# untitled.net
KiCad netlist of a schematic drawn in EAGLE
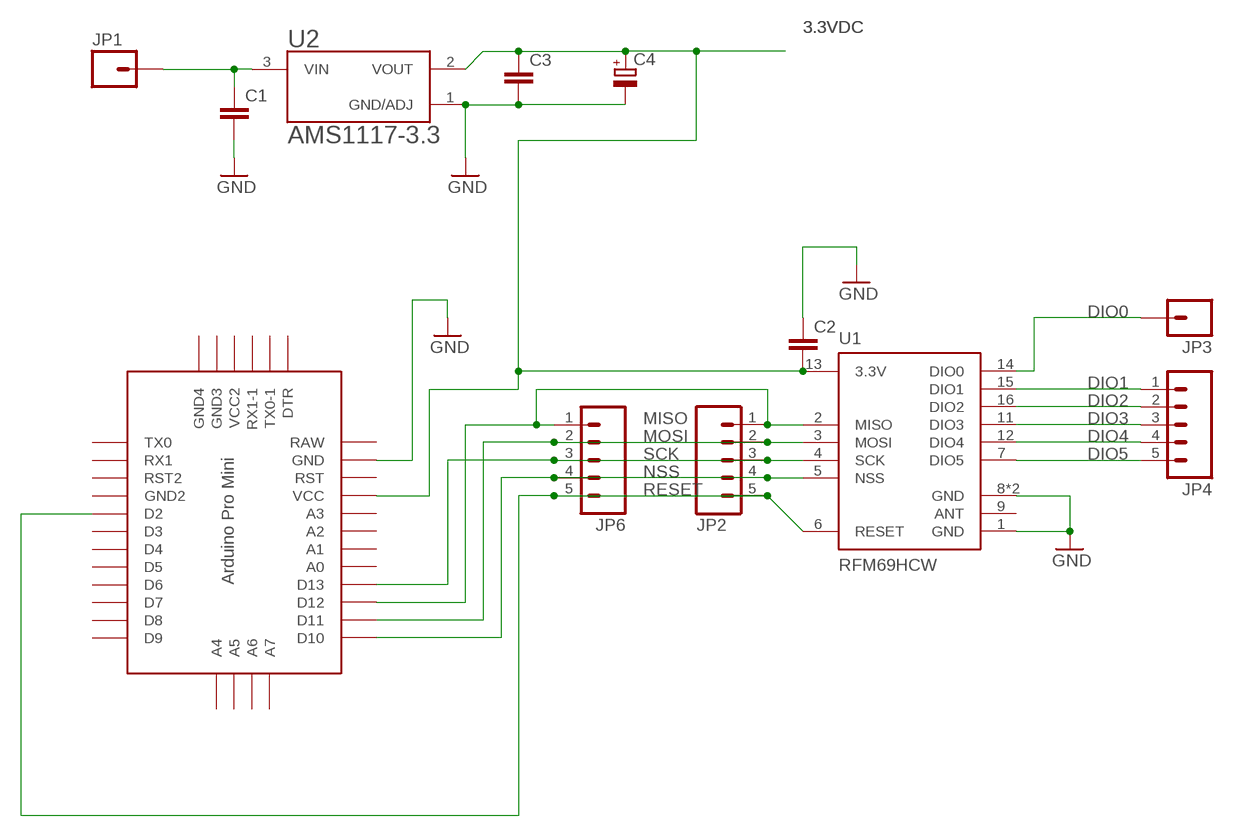
[diagram p0: schematic, sheet 1]

(export (version "E")
  (design (tool "Eeschema 10.0.6"))
  (components
    (comp (ref "C1")
      (value "C-EU025-030X050")
      (footprint "eagle-import:C025-030X050")
      (libsource (lib "eagle-import") (part "C-EU025-030X050"))
    )
    (comp (ref "C2")
      (value "C-EU025-030X050")
      (footprint "eagle-import:C025-030X050")
      (libsource (lib "eagle-import") (part "C-EU025-030X050"))
    )
    (comp (ref "C3")
      (value "C-EU025-030X050")
      (footprint "eagle-import:C025-030X050")
      (libsource (lib "eagle-import") (part "C-EU025-030X050"))
    )
    (comp (ref "C4")
      (value "CPOL-EUE5-8.5")
      (footprint "eagle-import:E5-8,5")
      (libsource (lib "eagle-import") (part "CPOL-EUE5-8.5"))
    )
    (comp (ref "JP1")
      (value "M01SMDNS")
      (footprint "eagle-import:1X01NS")
      (libsource (lib "eagle-import") (part "M01SMDNS"))
    )
    (comp (ref "JP2")
      (value "M05_ROUNDONLY_NOSILK")
      (footprint "eagle-import:1X05_ROUNDONLY_NOSILK")
      (libsource (lib "eagle-import") (part "M05_ROUNDONLY_NOSILK"))
    )
    (comp (ref "JP3")
      (value "M01SMDNS")
      (footprint "eagle-import:1X01NS")
      (libsource (lib "eagle-import") (part "M01SMDNS"))
    )
    (comp (ref "JP4")
      (value "M05_ROUNDONLY_NOSILK")
      (footprint "eagle-import:1X05_ROUNDONLY_NOSILK")
      (libsource (lib "eagle-import") (part "M05_ROUNDONLY_NOSILK"))
    )
    (comp (ref "JP6")
      (value "M05_ROUNDONLY_NOSILK")
      (footprint "eagle-import:1X05_ROUNDONLY_NOSILK")
      (libsource (lib "eagle-import") (part "M05_ROUNDONLY_NOSILK"))
    )
    (comp (ref "U$1")
      (value "PRO-MINI")
      (footprint "eagle-import:PRO-MINI")
      (libsource (lib "eagle-import") (part "PRO-MINI"))
    )
    (comp (ref "U1")
      (value "RFM69HCW")
      (footprint "eagle-import:RFM69HCW-XXXS2")
      (libsource (lib "eagle-import") (part "RFM69HCW"))
    )
    (comp (ref "U2")
      (value "AMS1117-3.3")
      (footprint "eagle-import:SOT229P700X180-4N")
      (fields (field (name "MF") "Advanced Monolithic Systems"))
      (libsource (lib "eagle-import") (part "AMS1117-3.3"))
    )
  )
  (nets
    (net (code "1") (name "/3.3VDC") (class "Default")
      (node (ref "C2") (pin "2") (pinfunction "2_2") (pintype "passive"))
      (node (ref "C3") (pin "1") (pinfunction "1_1") (pintype "passive"))
      (node (ref "C4") (pin "+") (pinfunction "+_+") (pintype "passive"))
      (node (ref "U$1") (pin "VCC") (pinfunction "VCC_VCC") (pintype "bidirectional"))
      (node (ref "U1") (pin "13") (pinfunction "3.3V_13") (pintype "power_in"))
      (node (ref "U2") (pin "2") (pinfunction "VOUT_2") (pintype "output"))
    )
    (net (code "2") (name "/DIO0") (class "Default")
      (node (ref "JP3") (pin "1") (pinfunction "1_1") (pintype "passive"))
      (node (ref "U1") (pin "14") (pinfunction "DIO0_14") (pintype "bidirectional"))
    )
    (net (code "3") (name "/DIO1") (class "Default")
      (node (ref "JP4") (pin "1") (pinfunction "1_1") (pintype "passive"))
      (node (ref "U1") (pin "15") (pinfunction "DIO1_15") (pintype "bidirectional"))
    )
    (net (code "4") (name "/DIO2") (class "Default")
      (node (ref "JP4") (pin "2") (pinfunction "2_2") (pintype "passive"))
      (node (ref "U1") (pin "16") (pinfunction "DIO2_16") (pintype "bidirectional"))
    )
    (net (code "5") (name "/DIO3") (class "Default")
      (node (ref "JP4") (pin "3") (pinfunction "3_3") (pintype "passive"))
      (node (ref "U1") (pin "11") (pinfunction "DIO3_11") (pintype "bidirectional"))
    )
    (net (code "6") (name "/DIO4") (class "Default")
      (node (ref "JP4") (pin "4") (pinfunction "4_4") (pintype "passive"))
      (node (ref "U1") (pin "12") (pinfunction "DIO4_12") (pintype "bidirectional"))
    )
    (net (code "7") (name "/DIO5") (class "Default")
      (node (ref "JP4") (pin "5") (pinfunction "5_5") (pintype "passive"))
      (node (ref "U1") (pin "7") (pinfunction "DIO5_7") (pintype "bidirectional"))
    )
    (net (code "8") (name "/MISO") (class "Default")
      (node (ref "JP2") (pin "1") (pinfunction "1_1") (pintype "passive"))
      (node (ref "JP6") (pin "1") (pinfunction "1_1") (pintype "passive"))
      (node (ref "U$1") (pin "D12") (pinfunction "D12_D12") (pintype "bidirectional"))
      (node (ref "U1") (pin "2") (pinfunction "MISO_2") (pintype "bidirectional"))
    )
    (net (code "9") (name "/MOSI") (class "Default")
      (node (ref "JP2") (pin "2") (pinfunction "2_2") (pintype "passive"))
      (node (ref "JP6") (pin "2") (pinfunction "2_2") (pintype "passive"))
      (node (ref "U$1") (pin "D11") (pinfunction "D11_D11") (pintype "bidirectional"))
      (node (ref "U1") (pin "3") (pinfunction "MOSI_3") (pintype "input"))
    )
    (net (code "10") (name "/NSS") (class "Default")
      (node (ref "JP2") (pin "4") (pinfunction "4_4") (pintype "passive"))
      (node (ref "JP6") (pin "4") (pinfunction "4_4") (pintype "passive"))
      (node (ref "U$1") (pin "D10") (pinfunction "D10_D10") (pintype "bidirectional"))
      (node (ref "U1") (pin "5") (pinfunction "NSS_5") (pintype "input"))
    )
    (net (code "11") (name "/RAW") (class "Default")
      (node (ref "U$1") (pin "RAW") (pinfunction "RAW_RAW") (pintype "power_in"))
    )
    (net (code "12") (name "/RESET") (class "Default")
      (node (ref "JP2") (pin "5") (pinfunction "5_5") (pintype "passive"))
      (node (ref "JP6") (pin "5") (pinfunction "5_5") (pintype "passive"))
      (node (ref "U$1") (pin "D2") (pinfunction "D2_D2") (pintype "bidirectional"))
      (node (ref "U1") (pin "6") (pinfunction "RESET_6") (pintype "input"))
    )
    (net (code "13") (name "/SCK") (class "Default")
      (node (ref "JP2") (pin "3") (pinfunction "3_3") (pintype "passive"))
      (node (ref "JP6") (pin "3") (pinfunction "3_3") (pintype "passive"))
      (node (ref "U$1") (pin "D13") (pinfunction "D13_D13") (pintype "bidirectional"))
      (node (ref "U1") (pin "4") (pinfunction "SCK_4") (pintype "input"))
    )
    (net (code "14") (name "GND") (class "Default")
      (node (ref "C1") (pin "2") (pinfunction "2_2") (pintype "passive"))
      (node (ref "C2") (pin "1") (pinfunction "1_1") (pintype "passive"))
      (node (ref "C3") (pin "2") (pinfunction "2_2") (pintype "passive"))
      (node (ref "C4") (pin "-") (pinfunction "-_-") (pintype "passive"))
      (node (ref "U$1") (pin "GND") (pinfunction "GND_GND") (pintype "input"))
      (node (ref "U1") (pin "1") (pinfunction "GND_1") (pintype "power_in"))
      (node (ref "U1") (pin "10") (pinfunction "GND_10") (pintype "power_in"))
      (node (ref "U1") (pin "8") (pinfunction "GND_8") (pintype "power_in"))
      (node (ref "U2") (pin "1") (pinfunction "GND/ADJ_1") (pintype "power_in"))
    )
    (net (code "15") (name "Net-(U2-VIN)") (class "Default")
      (node (ref "C1") (pin "1") (pinfunction "1_1") (pintype "passive"))
      (node (ref "JP1") (pin "1") (pinfunction "1_1") (pintype "passive"))
      (node (ref "U2") (pin "3") (pinfunction "VIN_3") (pintype "input"))
    )
    (net (code "16") (name "unconnected-(U$1-GND2-PadGND1)") (class "Default")
      (node (ref "U$1") (pin "GND1") (pinfunction "GND2_GND1") (pintype "bidirectional"))
    )
    (net (code "17") (name "unconnected-(U$1-GND4-PadGND2)") (class "Default")
      (node (ref "U$1") (pin "GND2") (pinfunction "GND4_GND2") (pintype "bidirectional"))
    )
    (net (code "18") (name "unconnected-(U$1-PadA0)") (class "Default")
      (node (ref "U$1") (pin "A0") (pinfunction "A0_A0") (pintype "bidirectional"))
    )
    (net (code "19") (name "unconnected-(U$1-PadA1)") (class "Default")
      (node (ref "U$1") (pin "A1") (pinfunction "A1_A1") (pintype "bidirectional"))
    )
    (net (code "20") (name "unconnected-(U$1-PadA2)") (class "Default")
      (node (ref "U$1") (pin "A2") (pinfunction "A2_A2") (pintype "bidirectional"))
    )
    (net (code "21") (name "unconnected-(U$1-PadA3)") (class "Default")
      (node (ref "U$1") (pin "A3") (pinfunction "A3_A3") (pintype "bidirectional"))
    )
    (net (code "22") (name "unconnected-(U$1-PadA4)") (class "Default")
      (node (ref "U$1") (pin "A4") (pinfunction "A4_A4") (pintype "bidirectional"))
    )
    (net (code "23") (name "unconnected-(U$1-PadA5)") (class "Default")
      (node (ref "U$1") (pin "A5") (pinfunction "A5_A5") (pintype "bidirectional"))
    )
    (net (code "24") (name "unconnected-(U$1-PadA6)") (class "Default")
      (node (ref "U$1") (pin "A6") (pinfunction "A6_A6") (pintype "bidirectional"))
    )
    (net (code "25") (name "unconnected-(U$1-PadA7)") (class "Default")
      (node (ref "U$1") (pin "A7") (pinfunction "A7_A7") (pintype "bidirectional"))
    )
    (net (code "26") (name "unconnected-(U$1-PadD3)") (class "Default")
      (node (ref "U$1") (pin "D3") (pinfunction "D3_D3") (pintype "bidirectional"))
    )
    (net (code "27") (name "unconnected-(U$1-PadD4)") (class "Default")
      (node (ref "U$1") (pin "D4") (pinfunction "D4_D4") (pintype "bidirectional"))
    )
    (net (code "28") (name "unconnected-(U$1-PadD5)") (class "Default")
      (node (ref "U$1") (pin "D5") (pinfunction "D5_D5") (pintype "bidirectional"))
    )
    (net (code "29") (name "unconnected-(U$1-PadD6)") (class "Default")
      (node (ref "U$1") (pin "D6") (pinfunction "D6_D6") (pintype "bidirectional"))
    )
    (net (code "30") (name "unconnected-(U$1-PadD7)") (class "Default")
      (node (ref "U$1") (pin "D7") (pinfunction "D7_D7") (pintype "bidirectional"))
    )
    (net (code "31") (name "unconnected-(U$1-PadD8)") (class "Default")
      (node (ref "U$1") (pin "D8") (pinfunction "D8_D8") (pintype "bidirectional"))
    )
    (net (code "32") (name "unconnected-(U$1-PadD9)") (class "Default")
      (node (ref "U$1") (pin "D9") (pinfunction "D9_D9") (pintype "bidirectional"))
    )
    (net (code "33") (name "unconnected-(U$1-PadDTR)") (class "Default")
      (node (ref "U$1") (pin "DTR") (pinfunction "DTR_DTR") (pintype "bidirectional"))
    )
    (net (code "34") (name "unconnected-(U$1-PadGND3)") (class "Default")
      (node (ref "U$1") (pin "GND3") (pinfunction "GND3_GND3") (pintype "bidirectional"))
    )
    (net (code "35") (name "unconnected-(U$1-PadRST)") (class "Default")
      (node (ref "U$1") (pin "RST") (pinfunction "RST_RST") (pintype "bidirectional"))
    )
    (net (code "36") (name "unconnected-(U$1-PadRX1)") (class "Default")
      (node (ref "U$1") (pin "RX1") (pinfunction "RX1_RX1") (pintype "bidirectional"))
    )
    (net (code "37") (name "unconnected-(U$1-PadRX1-1)") (class "Default")
      (node (ref "U$1") (pin "RX1-1") (pinfunction "RX1-1_RX1-1") (pintype "bidirectional"))
    )
    (net (code "38") (name "unconnected-(U$1-PadTX0)") (class "Default")
      (node (ref "U$1") (pin "TX0") (pinfunction "TX0_TX0") (pintype "bidirectional"))
    )
    (net (code "39") (name "unconnected-(U$1-PadTX0-1)") (class "Default")
      (node (ref "U$1") (pin "TX0-1") (pinfunction "TX0-1_TX0-1") (pintype "bidirectional"))
    )
    (net (code "40") (name "unconnected-(U$1-RST2-PadRST1)") (class "Default")
      (node (ref "U$1") (pin "RST1") (pinfunction "RST2_RST1") (pintype "bidirectional"))
    )
    (net (code "41") (name "unconnected-(U$1-VCC2-PadVCC1)") (class "Default")
      (node (ref "U$1") (pin "VCC1") (pinfunction "VCC2_VCC1") (pintype "bidirectional"))
    )
    (net (code "42") (name "unconnected-(U1-ANT-Pad9)") (class "Default")
      (node (ref "U1") (pin "9") (pinfunction "ANT_9") (pintype "passive"))
    )
  )
)
